# 8_CONNECTORS_MECH.net
KiCad netlist of a schematic drawn in Altium Designer
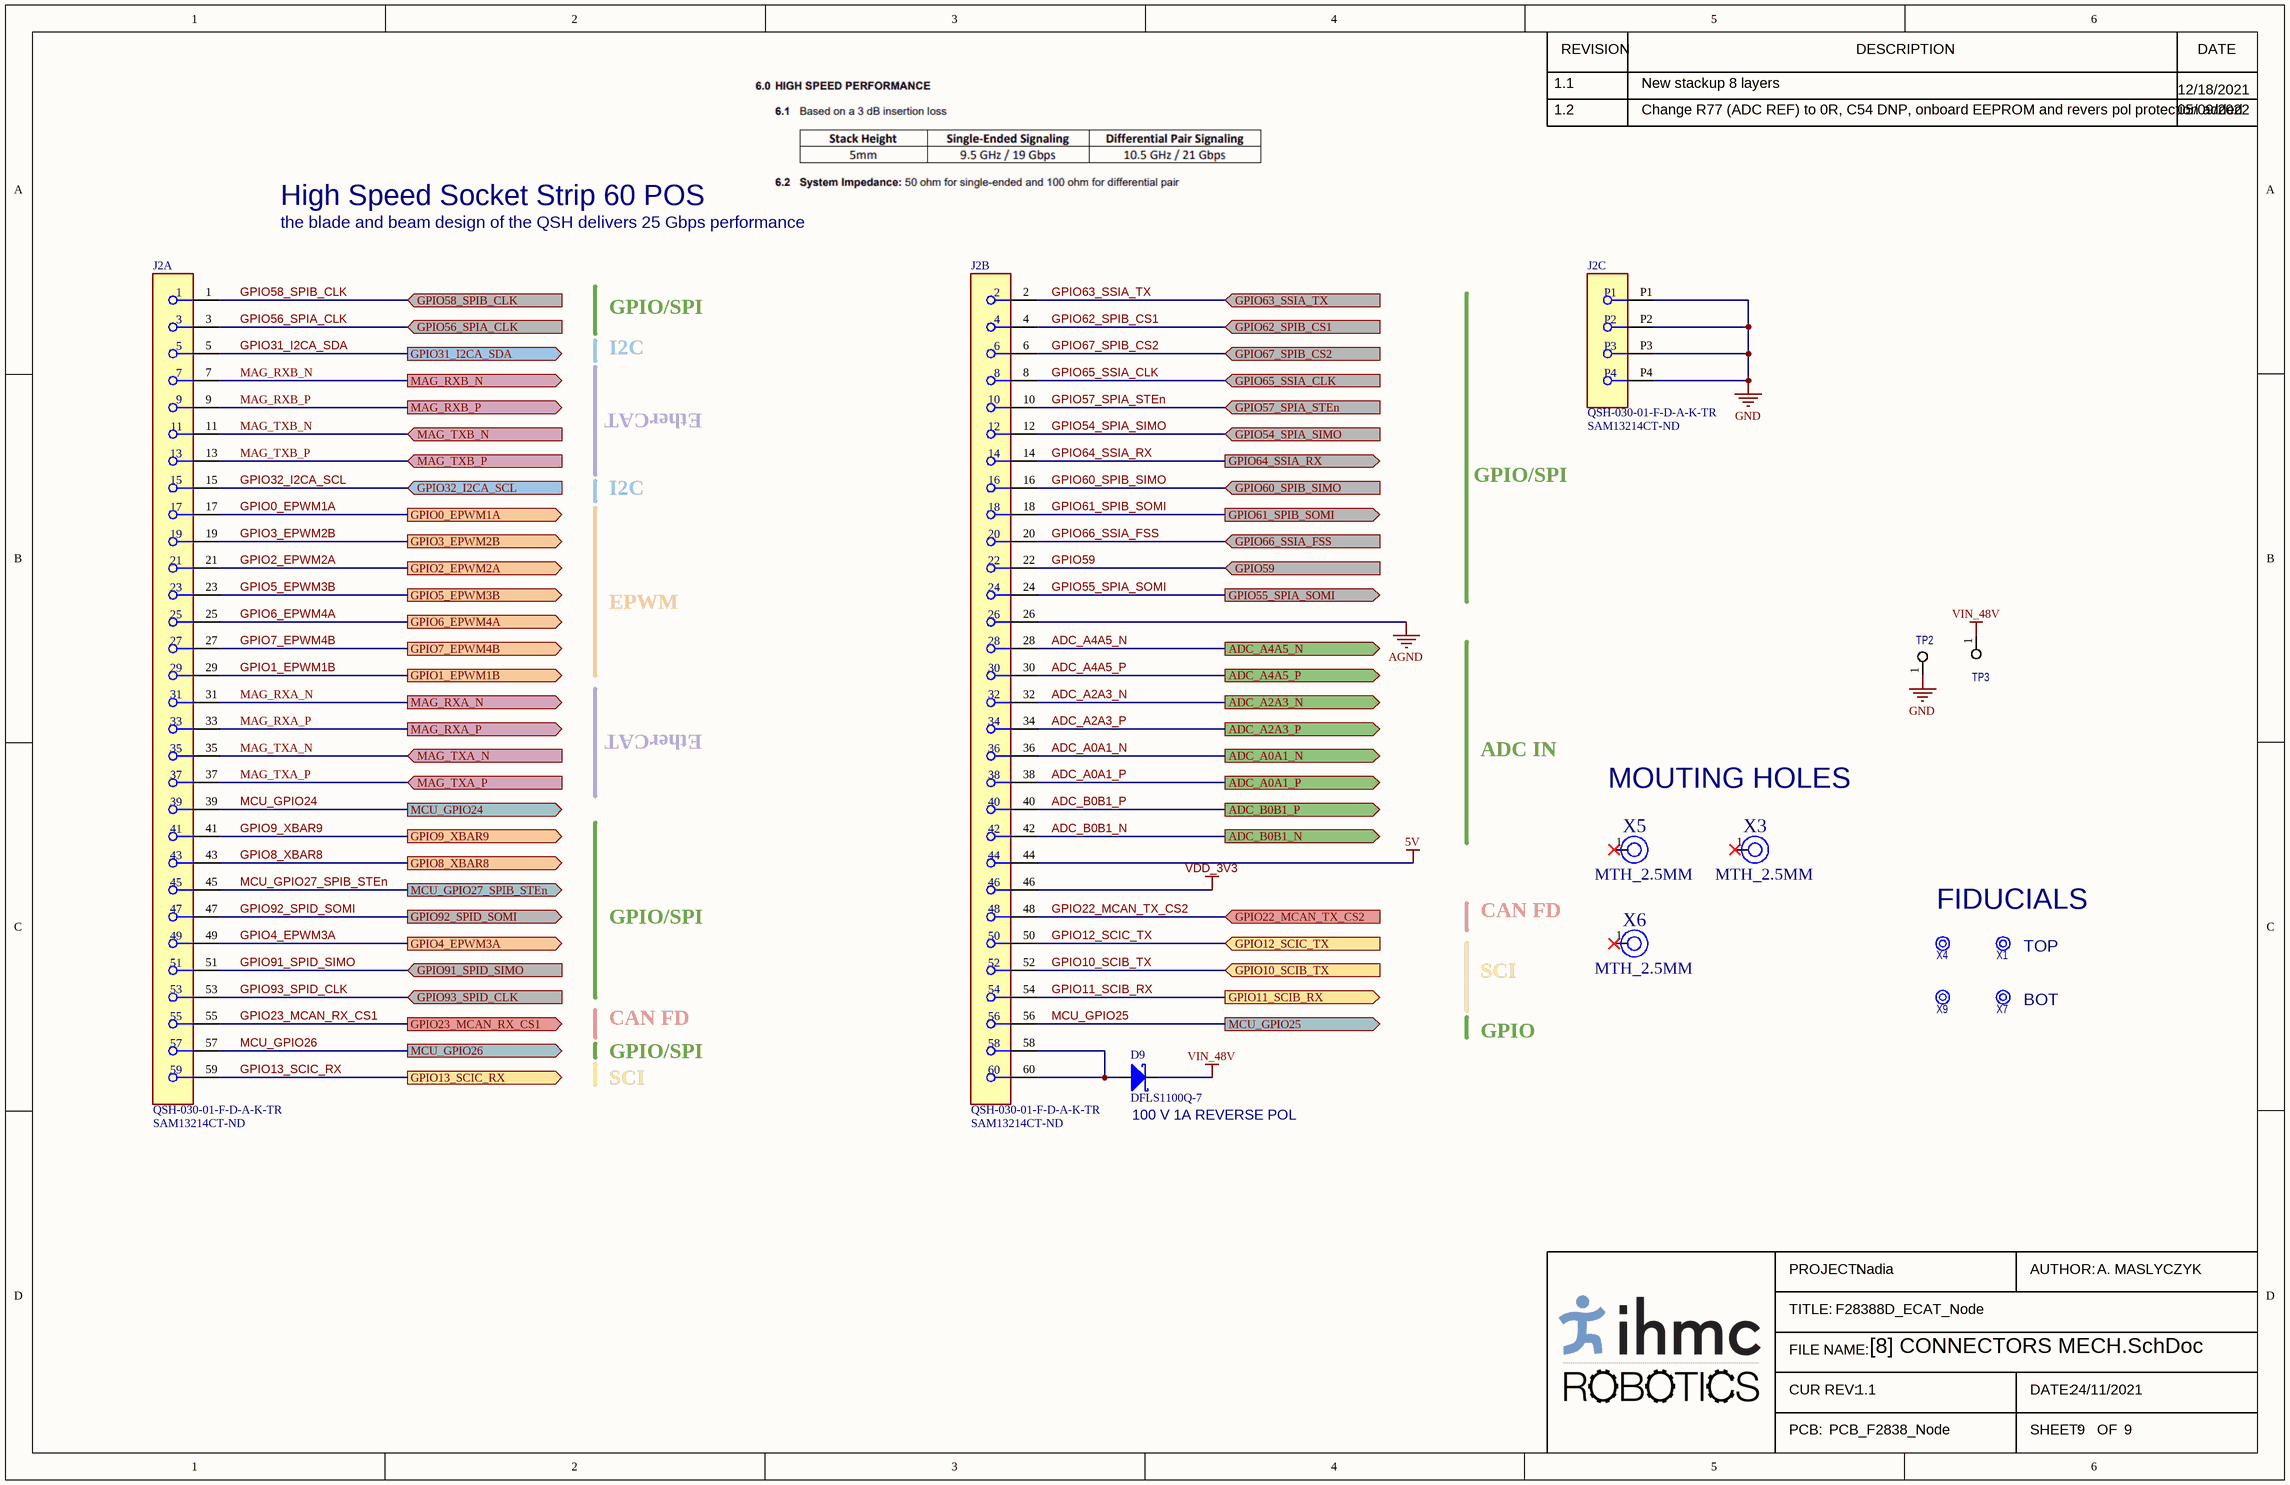
[diagram p0: [8] CONNECTORS MECH.SchDoc]

(export (version "E")
  (design (tool "Eeschema 10.0.6"))
  (components
    (comp (ref "D9")
      (value "DFLS1100Q-7")
      (footprint "DI_123")
      (description "Rectifier Diode Schottky 100V 1A Automotive 2-Pin PowerDI 123 T/R")
      (fields (field (name "MANUFACTURER") "Diodes"))
      (libsource (lib "IHMC_Altium_Lib") (part "DIODE_SCHOTTKY_100V_1A_DFLS1100Q-7"))
    )
    (comp (ref "J2")
      (value "QSH-030-01-F-D-A-K-TR")
      (footprint "FP-QSH-030-01-F-D-A-K-TR-MFG")
      (description "Conn Micro High Speed Socket Strip SKT 60 POS 0.5mm Solder ST SMD Automotive T/R")
      (fields (field (name "MANUFACTURER") "Samtec") (field (name "SUPPLIER PART NUMBER 1") "SAM13214CT-ND"))
      (libsource (lib "IHMC_Altium_Lib") (part "QSH-030-01-F-D-A_60PINS_CON"))
    )
    (comp (ref "TP2")
      (value "TP_SMD")
      (footprint "TP_5019")
      (description "Test point SMD")
      (libsource (lib "IHMC_Altium_Lib") (part "TP_SMD_1MM"))
    )
    (comp (ref "TP3")
      (value "TP_SMD")
      (footprint "TP_5019")
      (description "Test point SMD")
      (libsource (lib "IHMC_Altium_Lib") (part "TP_SMD_1MM"))
    )
    (comp (ref "X1")
      (value "FIDUCIAL")
      (footprint "FIDUCIAL")
      (libsource (lib "IHMC_Altium_Lib") (part "FIDUCIAL"))
    )
    (comp (ref "X3")
      (value "MTH_2.5MM")
      (footprint "MTH-M2.5mm")
      (fields (field (name "PKG_TYPE") "MTH_2.5MM"))
      (libsource (lib "IHMC_Altium_Lib") (part "MTH_2.5MM"))
    )
    (comp (ref "X4")
      (value "FIDUCIAL")
      (footprint "FIDUCIAL")
      (libsource (lib "IHMC_Altium_Lib") (part "FIDUCIAL"))
    )
    (comp (ref "X5")
      (value "MTH_2.5MM")
      (footprint "MTH-M2.5mm")
      (fields (field (name "PKG_TYPE") "MTH_2.5MM"))
      (libsource (lib "IHMC_Altium_Lib") (part "MTH_2.5MM"))
    )
    (comp (ref "X6")
      (value "MTH_2.5MM")
      (footprint "MTH-M2.5mm")
      (fields (field (name "PKG_TYPE") "MTH_2.5MM"))
      (libsource (lib "IHMC_Altium_Lib") (part "MTH_2.5MM"))
    )
    (comp (ref "X7")
      (value "FIDUCIAL")
      (footprint "FIDUCIAL")
      (libsource (lib "IHMC_Altium_Lib") (part "FIDUCIAL"))
    )
    (comp (ref "X9")
      (value "FIDUCIAL")
      (footprint "FIDUCIAL")
      (libsource (lib "IHMC_Altium_Lib") (part "FIDUCIAL"))
    )
  )
  (nets
    (net (code "1") (name "/ADC_A0A1_N") (class "Default")
      (node (ref "J2") (pin "36") (pinfunction "36_36") (pintype "passive"))
    )
    (net (code "2") (name "/ADC_A0A1_P") (class "Default")
      (node (ref "J2") (pin "38") (pinfunction "38_38") (pintype "passive"))
    )
    (net (code "3") (name "/ADC_A2A3_N") (class "Default")
      (node (ref "J2") (pin "32") (pinfunction "32_32") (pintype "passive"))
    )
    (net (code "4") (name "/ADC_A2A3_P") (class "Default")
      (node (ref "J2") (pin "34") (pinfunction "34_34") (pintype "passive"))
    )
    (net (code "5") (name "/ADC_A4A5_N") (class "Default")
      (node (ref "J2") (pin "28") (pinfunction "28_28") (pintype "passive"))
    )
    (net (code "6") (name "/ADC_A4A5_P") (class "Default")
      (node (ref "J2") (pin "30") (pinfunction "30_30") (pintype "passive"))
    )
    (net (code "7") (name "/ADC_B0B1_N") (class "Default")
      (node (ref "J2") (pin "42") (pinfunction "42_42") (pintype "passive"))
    )
    (net (code "8") (name "/ADC_B0B1_P") (class "Default")
      (node (ref "J2") (pin "40") (pinfunction "40_40") (pintype "passive"))
    )
    (net (code "9") (name "/GPIO0_EPWM1A") (class "Default")
      (node (ref "J2") (pin "17") (pinfunction "17_17") (pintype "passive"))
    )
    (net (code "10") (name "/GPIO1_EPWM1B") (class "Default")
      (node (ref "J2") (pin "29") (pinfunction "29_29") (pintype "passive"))
    )
    (net (code "11") (name "/GPIO2_EPWM2A") (class "Default")
      (node (ref "J2") (pin "21") (pinfunction "21_21") (pintype "passive"))
    )
    (net (code "12") (name "/GPIO3_EPWM2B") (class "Default")
      (node (ref "J2") (pin "19") (pinfunction "19_19") (pintype "passive"))
    )
    (net (code "13") (name "/GPIO4_EPWM3A") (class "Default")
      (node (ref "J2") (pin "49") (pinfunction "49_49") (pintype "passive"))
    )
    (net (code "14") (name "/GPIO5_EPWM3B") (class "Default")
      (node (ref "J2") (pin "23") (pinfunction "23_23") (pintype "passive"))
    )
    (net (code "15") (name "/GPIO6_EPWM4A") (class "Default")
      (node (ref "J2") (pin "25") (pinfunction "25_25") (pintype "passive"))
    )
    (net (code "16") (name "/GPIO7_EPWM4B") (class "Default")
      (node (ref "J2") (pin "27") (pinfunction "27_27") (pintype "passive"))
    )
    (net (code "17") (name "/GPIO8_XBAR8") (class "Default")
      (node (ref "J2") (pin "43") (pinfunction "43_43") (pintype "passive"))
    )
    (net (code "18") (name "/GPIO9_XBAR9") (class "Default")
      (node (ref "J2") (pin "41") (pinfunction "41_41") (pintype "passive"))
    )
    (net (code "19") (name "/GPIO10_SCIB_TX") (class "Default")
      (node (ref "J2") (pin "52") (pinfunction "52_52") (pintype "passive"))
    )
    (net (code "20") (name "/GPIO11_SCIB_RX") (class "Default")
      (node (ref "J2") (pin "54") (pinfunction "54_54") (pintype "passive"))
    )
    (net (code "21") (name "/GPIO12_SCIC_TX") (class "Default")
      (node (ref "J2") (pin "50") (pinfunction "50_50") (pintype "passive"))
    )
    (net (code "22") (name "/GPIO13_SCIC_RX") (class "Default")
      (node (ref "J2") (pin "59") (pinfunction "59_59") (pintype "passive"))
    )
    (net (code "23") (name "/GPIO22_MCAN_TX_CS2") (class "Default")
      (node (ref "J2") (pin "48") (pinfunction "48_48") (pintype "passive"))
    )
    (net (code "24") (name "/GPIO23_MCAN_RX_CS1") (class "Default")
      (node (ref "J2") (pin "55") (pinfunction "55_55") (pintype "passive"))
    )
    (net (code "25") (name "/GPIO31_I2CA_SDA") (class "Default")
      (node (ref "J2") (pin "5") (pinfunction "5_5") (pintype "passive"))
    )
    (net (code "26") (name "/GPIO32_I2CA_SCL") (class "Default")
      (node (ref "J2") (pin "15") (pinfunction "15_15") (pintype "passive"))
    )
    (net (code "27") (name "/GPIO54_SPIA_SIMO") (class "Default")
      (node (ref "J2") (pin "12") (pinfunction "12_12") (pintype "passive"))
    )
    (net (code "28") (name "/GPIO55_SPIA_SOMI") (class "Default")
      (node (ref "J2") (pin "24") (pinfunction "24_24") (pintype "passive"))
    )
    (net (code "29") (name "/GPIO56_SPIA_CLK") (class "Default")
      (node (ref "J2") (pin "3") (pinfunction "3_3") (pintype "passive"))
    )
    (net (code "30") (name "/GPIO57_SPIA_STEn") (class "Default")
      (node (ref "J2") (pin "10") (pinfunction "10_10") (pintype "passive"))
    )
    (net (code "31") (name "/GPIO58_SPIB_CLK") (class "Default")
      (node (ref "J2") (pin "1") (pinfunction "1_1") (pintype "passive"))
    )
    (net (code "32") (name "/GPIO59") (class "Default")
      (node (ref "J2") (pin "22") (pinfunction "22_22") (pintype "passive"))
    )
    (net (code "33") (name "/GPIO60_SPIB_SIMO") (class "Default")
      (node (ref "J2") (pin "16") (pinfunction "16_16") (pintype "passive"))
    )
    (net (code "34") (name "/GPIO61_SPIB_SOMI") (class "Default")
      (node (ref "J2") (pin "18") (pinfunction "18_18") (pintype "passive"))
    )
    (net (code "35") (name "/GPIO62_SPIB_CS1") (class "Default")
      (node (ref "J2") (pin "4") (pinfunction "4_4") (pintype "passive"))
    )
    (net (code "36") (name "/GPIO63_SSIA_TX") (class "Default")
      (node (ref "J2") (pin "2") (pinfunction "2_2") (pintype "passive"))
    )
    (net (code "37") (name "/GPIO64_SSIA_RX") (class "Default")
      (node (ref "J2") (pin "14") (pinfunction "14_14") (pintype "passive"))
    )
    (net (code "38") (name "/GPIO65_SSIA_CLK") (class "Default")
      (node (ref "J2") (pin "8") (pinfunction "8_8") (pintype "passive"))
    )
    (net (code "39") (name "/GPIO66_SSIA_FSS") (class "Default")
      (node (ref "J2") (pin "20") (pinfunction "20_20") (pintype "passive"))
    )
    (net (code "40") (name "/GPIO67_SPIB_CS2") (class "Default")
      (node (ref "J2") (pin "6") (pinfunction "6_6") (pintype "passive"))
    )
    (net (code "41") (name "/GPIO91_SPID_SIMO") (class "Default")
      (node (ref "J2") (pin "51") (pinfunction "51_51") (pintype "passive"))
    )
    (net (code "42") (name "/GPIO92_SPID_SOMI") (class "Default")
      (node (ref "J2") (pin "47") (pinfunction "47_47") (pintype "passive"))
    )
    (net (code "43") (name "/GPIO93_SPID_CLK") (class "Default")
      (node (ref "J2") (pin "53") (pinfunction "53_53") (pintype "passive"))
    )
    (net (code "44") (name "/MAG_RXA_N") (class "Default")
      (node (ref "J2") (pin "31") (pinfunction "31_31") (pintype "passive"))
    )
    (net (code "45") (name "/MAG_RXA_P") (class "Default")
      (node (ref "J2") (pin "33") (pinfunction "33_33") (pintype "passive"))
    )
    (net (code "46") (name "/MAG_RXB_N") (class "Default")
      (node (ref "J2") (pin "7") (pinfunction "7_7") (pintype "passive"))
    )
    (net (code "47") (name "/MAG_RXB_P") (class "Default")
      (node (ref "J2") (pin "9") (pinfunction "9_9") (pintype "passive"))
    )
    (net (code "48") (name "/MAG_TXA_N") (class "Default")
      (node (ref "J2") (pin "35") (pinfunction "35_35") (pintype "passive"))
    )
    (net (code "49") (name "/MAG_TXA_P") (class "Default")
      (node (ref "J2") (pin "37") (pinfunction "37_37") (pintype "passive"))
    )
    (net (code "50") (name "/MAG_TXB_N") (class "Default")
      (node (ref "J2") (pin "11") (pinfunction "11_11") (pintype "passive"))
    )
    (net (code "51") (name "/MAG_TXB_P") (class "Default")
      (node (ref "J2") (pin "13") (pinfunction "13_13") (pintype "passive"))
    )
    (net (code "52") (name "/MCU_GPIO24") (class "Default")
      (node (ref "J2") (pin "39") (pinfunction "39_39") (pintype "passive"))
    )
    (net (code "53") (name "/MCU_GPIO25") (class "Default")
      (node (ref "J2") (pin "56") (pinfunction "56_56") (pintype "passive"))
    )
    (net (code "54") (name "/MCU_GPIO26") (class "Default")
      (node (ref "J2") (pin "57") (pinfunction "57_57") (pintype "passive"))
    )
    (net (code "55") (name "/MCU_GPIO27_SPIB_STEn") (class "Default")
      (node (ref "J2") (pin "45") (pinfunction "45_45") (pintype "passive"))
    )
    (net (code "56") (name "5V") (class "Default")
      (node (ref "J2") (pin "44") (pinfunction "44_44") (pintype "passive"))
    )
    (net (code "57") (name "AGND") (class "Default")
      (node (ref "J2") (pin "26") (pinfunction "26_26") (pintype "passive"))
    )
    (net (code "58") (name "GND") (class "Default")
      (node (ref "J2") (pin "P1") (pinfunction "P1_P1") (pintype "power_in"))
      (node (ref "J2") (pin "P2") (pinfunction "P2_P2") (pintype "power_in"))
      (node (ref "J2") (pin "P3") (pinfunction "P3_P3") (pintype "power_in"))
      (node (ref "J2") (pin "P4") (pinfunction "P4_P4") (pintype "power_in"))
      (node (ref "TP2") (pin "1") (pinfunction "IN_1") (pintype "passive"))
    )
    (net (code "59") (name "Net-(D9-A)") (class "Default")
      (node (ref "D9") (pin "2") (pinfunction "A_2") (pintype "passive"))
      (node (ref "J2") (pin "58") (pinfunction "58_58") (pintype "passive"))
      (node (ref "J2") (pin "60") (pinfunction "60_60") (pintype "passive"))
    )
    (net (code "60") (name "VDD_3V3") (class "Default")
      (node (ref "J2") (pin "46") (pinfunction "46_46") (pintype "passive"))
    )
    (net (code "61") (name "VIN_48V") (class "Default")
      (node (ref "D9") (pin "1") (pinfunction "K_1") (pintype "passive"))
      (node (ref "TP3") (pin "1") (pinfunction "IN_1") (pintype "passive"))
    )
    (net (code "62") (name "unconnected-(X3-Pad1)") (class "Default")
      (node (ref "X3") (pin "1") (pinfunction "1_1") (pintype "passive+no_connect"))
    )
    (net (code "63") (name "unconnected-(X5-Pad1)") (class "Default")
      (node (ref "X5") (pin "1") (pinfunction "1_1") (pintype "passive+no_connect"))
    )
    (net (code "64") (name "unconnected-(X6-Pad1)") (class "Default")
      (node (ref "X6") (pin "1") (pinfunction "1_1") (pintype "passive+no_connect"))
    )
  )
)
